# Arrows_Keypad.net
KiCad netlist of a schematic drawn in Altium Designer
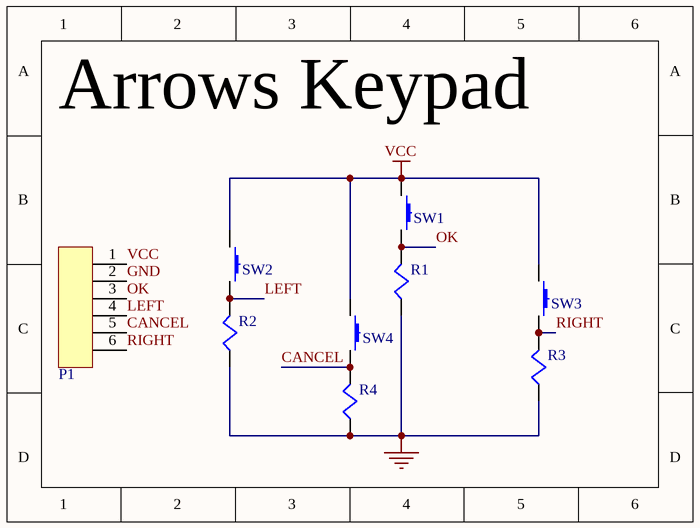
[diagram p0: Arrows Keypad.SchDoc]

(export (version "E")
  (design (tool "Eeschema 10.0.6"))
  (components
    (comp (ref "P1")
      (value "Header bounded 6 Pins")
      (footprint "Header Male 2.54mm 6 Pins TH Right")
      (fields (field (name "MANUFACTURER") "3M"))
      (libsource (lib "MyLib") (part "Terminal_Block_6Pos"))
    )
    (comp (ref "R1")
      (value "10K 0.25W")
      (footprint "Res 7.62mm H TH")
      (description "Resistors")
      (fields
        (field (name "MANUFACTURER") "Yageo")
        (field (name "MANUFACTURER PART NUMBER") "CFR-25JB-52-100K")
      )
      (libsource (lib "MyLib") (part "Resistors_Single"))
    )
    (comp (ref "R2")
      (value "10K 0.25W")
      (footprint "Res 7.62mm H TH")
      (description "Resistors")
      (fields
        (field (name "MANUFACTURER") "Yageo")
        (field (name "MANUFACTURER PART NUMBER") "CFR-25JB-52-100K")
      )
      (libsource (lib "MyLib") (part "Resistors_Single"))
    )
    (comp (ref "R3")
      (value "10K 0.25W")
      (footprint "Res 7.62mm H TH")
      (description "Resistors")
      (fields
        (field (name "MANUFACTURER") "Yageo")
        (field (name "MANUFACTURER PART NUMBER") "CFR-25JB-52-100K")
      )
      (libsource (lib "MyLib") (part "Resistors_Single"))
    )
    (comp (ref "R4")
      (value "10K 0.25W")
      (footprint "Res 7.62mm H TH")
      (description "Resistors")
      (fields
        (field (name "MANUFACTURER") "Yageo")
        (field (name "MANUFACTURER PART NUMBER") "CFR-25JB-52-100K")
      )
      (libsource (lib "MyLib") (part "Resistors_Single"))
    )
    (comp (ref "SW1")
      (value "12*12 DIP tactile Green")
      (footprint "Tactile 12*12 TH Green Omron")
      (description "Switches")
      (fields
        (field (name "MANUFACTURER") "E-Switch")
        (field (name "MANUFACTURER PART NUMBER") "TL1105LF160Q")
      )
      (libsource (lib "MyLib") (part "Switches_2Pos"))
    )
    (comp (ref "SW2")
      (value "12*12 DIP tactile Yellow")
      (footprint "Tactile 12*12 TH Yellow Omron")
      (description "Switches")
      (fields
        (field (name "MANUFACTURER") "E-Switch")
        (field (name "MANUFACTURER PART NUMBER") "TL1105LF160Q")
      )
      (libsource (lib "MyLib") (part "Switches_2Pos"))
    )
    (comp (ref "SW3")
      (value "12*12 DIP tactile Yellow")
      (footprint "Tactile 12*12 TH Yellow Omron")
      (description "Switches")
      (fields
        (field (name "MANUFACTURER") "E-Switch")
        (field (name "MANUFACTURER PART NUMBER") "TL1105LF160Q")
      )
      (libsource (lib "MyLib") (part "Switches_2Pos"))
    )
    (comp (ref "SW4")
      (value "12*12 DIP tactile Red")
      (footprint "Tactile 12*12 TH Red Omron")
      (description "Switches")
      (fields
        (field (name "MANUFACTURER") "E-Switch")
        (field (name "MANUFACTURER PART NUMBER") "TL1105LF160Q")
      )
      (libsource (lib "MyLib") (part "Switches_2Pos"))
    )
  )
  (nets
    (net (code "1") (name "/CANCEL") (class "Default")
      (node (ref "P1") (pin "5") (pinfunction "5_5") (pintype "passive"))
      (node (ref "R4") (pin "2") (pinfunction "2_2") (pintype "passive"))
      (node (ref "SW4") (pin "2") (pinfunction "2_2") (pintype "passive"))
    )
    (net (code "2") (name "/LEFT") (class "Default")
      (node (ref "P1") (pin "4") (pinfunction "4_4") (pintype "passive"))
      (node (ref "R2") (pin "2") (pinfunction "2_2") (pintype "passive"))
      (node (ref "SW2") (pin "2") (pinfunction "2_2") (pintype "passive"))
    )
    (net (code "3") (name "/OK") (class "Default")
      (node (ref "P1") (pin "3") (pinfunction "3_3") (pintype "passive"))
      (node (ref "R1") (pin "2") (pinfunction "2_2") (pintype "passive"))
      (node (ref "SW1") (pin "2") (pinfunction "2_2") (pintype "passive"))
    )
    (net (code "4") (name "/RIGHT") (class "Default")
      (node (ref "P1") (pin "6") (pinfunction "6_6") (pintype "passive"))
      (node (ref "R3") (pin "2") (pinfunction "2_2") (pintype "passive"))
      (node (ref "SW3") (pin "2") (pinfunction "2_2") (pintype "passive"))
    )
    (net (code "5") (name "GND") (class "Default")
      (node (ref "P1") (pin "2") (pinfunction "2_2") (pintype "passive"))
      (node (ref "R1") (pin "1") (pinfunction "1_1") (pintype "passive"))
      (node (ref "R2") (pin "1") (pinfunction "1_1") (pintype "passive"))
      (node (ref "R3") (pin "1") (pinfunction "1_1") (pintype "passive"))
      (node (ref "R4") (pin "1") (pinfunction "1_1") (pintype "passive"))
    )
    (net (code "6") (name "VCC") (class "Default")
      (node (ref "P1") (pin "1") (pinfunction "1_1") (pintype "passive"))
      (node (ref "SW1") (pin "1") (pinfunction "1_1") (pintype "passive"))
      (node (ref "SW2") (pin "1") (pinfunction "1_1") (pintype "passive"))
      (node (ref "SW3") (pin "1") (pinfunction "1_1") (pintype "passive"))
      (node (ref "SW4") (pin "1") (pinfunction "1_1") (pintype "passive"))
    )
  )
)
